# Watering_System_3_1.net
KiCad netlist of a schematic drawn in EAGLE
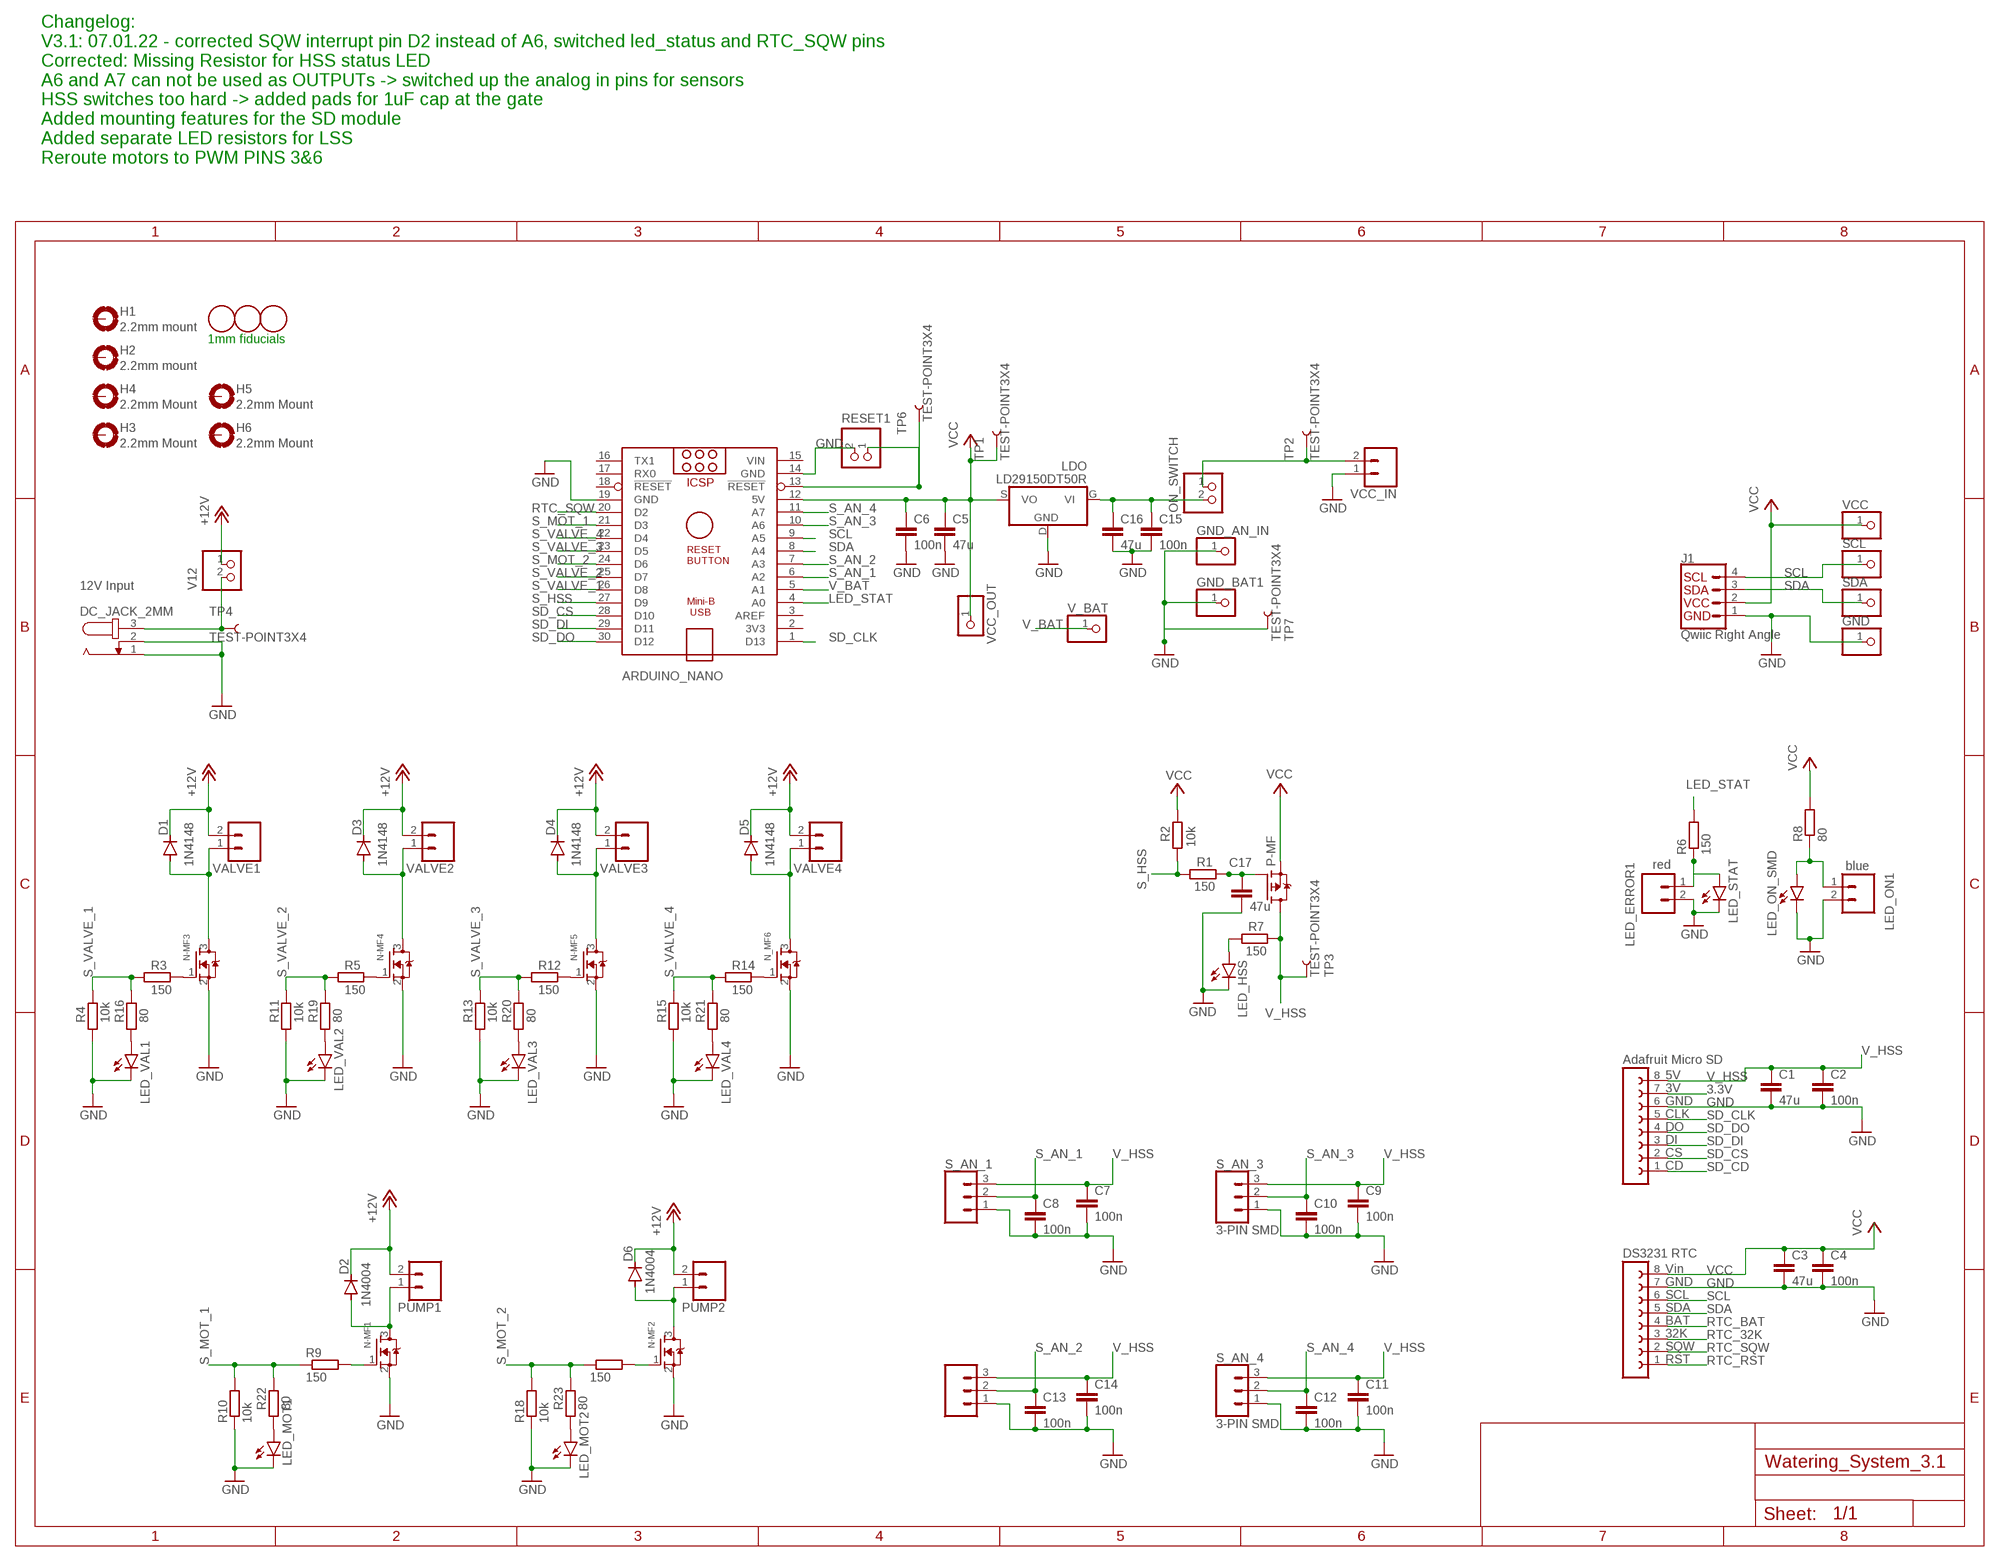
[diagram p0: schematic, sheet 1]

(export (version "E")
  (design (tool "Eeschema 10.0.6"))
  (components
    (comp (ref "ARDUINO_NANO")
      (value "ARDUINO_NANO")
      (footprint "eagle-import:ARDUINO_NANO")
      (libsource (lib "eagle-import") (part "ARDUINO_NANO"))
    )
    (comp (ref "C1")
      (value "47u")
      (footprint "eagle-import:C0805")
      (libsource (lib "eagle-import") (part "C-EUC0805"))
    )
    (comp (ref "C2")
      (value "100n")
      (footprint "eagle-import:C0805")
      (libsource (lib "eagle-import") (part "C-EUC0805"))
    )
    (comp (ref "C3")
      (value "47u")
      (footprint "eagle-import:C0805")
      (libsource (lib "eagle-import") (part "C-EUC0805"))
    )
    (comp (ref "C4")
      (value "100n")
      (footprint "eagle-import:C0805")
      (libsource (lib "eagle-import") (part "C-EUC0805"))
    )
    (comp (ref "C5")
      (value "47u")
      (footprint "eagle-import:C0805")
      (libsource (lib "eagle-import") (part "C-EUC0805"))
    )
    (comp (ref "C6")
      (value "100n")
      (footprint "eagle-import:C0805")
      (libsource (lib "eagle-import") (part "C-EUC0805"))
    )
    (comp (ref "C7")
      (value "100n")
      (footprint "eagle-import:C0805")
      (libsource (lib "eagle-import") (part "C-EUC0805"))
    )
    (comp (ref "C8")
      (value "100n")
      (footprint "eagle-import:C0805")
      (libsource (lib "eagle-import") (part "C-EUC0805"))
    )
    (comp (ref "C9")
      (value "100n")
      (footprint "eagle-import:C0805")
      (libsource (lib "eagle-import") (part "C-EUC0805"))
    )
    (comp (ref "C10")
      (value "100n")
      (footprint "eagle-import:C0805")
      (libsource (lib "eagle-import") (part "C-EUC0805"))
    )
    (comp (ref "C11")
      (value "100n")
      (footprint "eagle-import:C0805")
      (libsource (lib "eagle-import") (part "C-EUC0805"))
    )
    (comp (ref "C12")
      (value "100n")
      (footprint "eagle-import:C0805")
      (libsource (lib "eagle-import") (part "C-EUC0805"))
    )
    (comp (ref "C13")
      (value "100n")
      (footprint "eagle-import:C0805")
      (libsource (lib "eagle-import") (part "C-EUC0805"))
    )
    (comp (ref "C14")
      (value "100n")
      (footprint "eagle-import:C0805")
      (libsource (lib "eagle-import") (part "C-EUC0805"))
    )
    (comp (ref "C15")
      (value "100n")
      (footprint "eagle-import:C0805")
      (libsource (lib "eagle-import") (part "C-EUC0805"))
    )
    (comp (ref "C16")
      (value "47u")
      (footprint "eagle-import:C0805")
      (libsource (lib "eagle-import") (part "C-EUC0805"))
    )
    (comp (ref "C17")
      (value "47u")
      (footprint "eagle-import:C0805")
      (libsource (lib "eagle-import") (part "C-EUC0805"))
    )
    (comp (ref "D1")
      (value "1N4148")
      (footprint "eagle-import:DO35-7")
      (libsource (lib "eagle-import") (part "1N4148DO35-7"))
    )
    (comp (ref "D2")
      (value "1N4004")
      (footprint "eagle-import:DO41-10")
      (libsource (lib "eagle-import") (part "1N4004"))
    )
    (comp (ref "D3")
      (value "1N4148")
      (footprint "eagle-import:DO35-7")
      (libsource (lib "eagle-import") (part "1N4148DO35-7"))
    )
    (comp (ref "D4")
      (value "1N4148")
      (footprint "eagle-import:DO35-7")
      (libsource (lib "eagle-import") (part "1N4148DO35-7"))
    )
    (comp (ref "D5")
      (value "1N4148")
      (footprint "eagle-import:DO35-7")
      (libsource (lib "eagle-import") (part "1N4148DO35-7"))
    )
    (comp (ref "D6")
      (value "1N4004")
      (footprint "eagle-import:DO41-10")
      (libsource (lib "eagle-import") (part "1N4004"))
    )
    (comp (ref "DC_JACK_2MM")
      (value "12V Input")
      (footprint "eagle-import:SPC4077")
      (libsource (lib "eagle-import") (part "JACK-PLUG0"))
    )
    (comp (ref "GND")
      (value "PINHD-1X1")
      (footprint "eagle-import:1X01")
      (libsource (lib "eagle-import") (part "PINHD-1X1"))
    )
    (comp (ref "GND_AN_IN")
      (value "PINHD-1X1")
      (footprint "eagle-import:1X01")
      (libsource (lib "eagle-import") (part "PINHD-1X1"))
    )
    (comp (ref "GND_BAT1")
      (value "PINHD-1X1")
      (footprint "eagle-import:1X01")
      (libsource (lib "eagle-import") (part "PINHD-1X1"))
    )
    (comp (ref "H1")
      (value "2.2mm mount")
      (footprint "eagle-import:2,2-PAD")
      (libsource (lib "eagle-import") (part "MOUNT-PAD-ROUND2.8"))
    )
    (comp (ref "H2")
      (value "2.2mm mount")
      (footprint "eagle-import:2,2-PAD")
      (libsource (lib "eagle-import") (part "MOUNT-PAD-ROUND2.8"))
    )
    (comp (ref "H3")
      (value "2.2mm Mount")
      (footprint "eagle-import:2,2-PAD")
      (libsource (lib "eagle-import") (part "MOUNT-PAD-ROUND2.8"))
    )
    (comp (ref "H4")
      (value "2.2mm Mount")
      (footprint "eagle-import:2,2-PAD")
      (libsource (lib "eagle-import") (part "MOUNT-PAD-ROUND2.8"))
    )
    (comp (ref "H5")
      (value "2.2mm Mount")
      (footprint "eagle-import:2,2-PAD")
      (libsource (lib "eagle-import") (part "MOUNT-PAD-ROUND2.8"))
    )
    (comp (ref "H6")
      (value "2.2mm Mount")
      (footprint "eagle-import:2,2-PAD")
      (libsource (lib "eagle-import") (part "MOUNT-PAD-ROUND2.8"))
    )
    (comp (ref "J1")
      (value "Qwiic Right Angle")
      (footprint "eagle-import:1X04_1MM_RA")
      (libsource (lib "eagle-import") (part "I2C_STANDARDQWIIC"))
    )
    (comp (ref "LDO")
      (value "LD29150DT50R")
      (footprint "eagle-import:DPACK_2")
      (libsource (lib "eagle-import") (part "LD29150DT50R"))
    )
    (comp (ref "LED_ERROR1")
      (value "red")
      (footprint "eagle-import:1X02")
      (libsource (lib "eagle-import") (part "CONN_02"))
    )
    (comp (ref "LED_HSS")
      (value "LEDCHIPLED_0805")
      (footprint "eagle-import:CHIPLED_0805")
      (libsource (lib "eagle-import") (part "LEDCHIPLED_0805"))
    )
    (comp (ref "LED_MOT1")
      (value "LEDCHIPLED_0805")
      (footprint "eagle-import:CHIPLED_0805")
      (libsource (lib "eagle-import") (part "LEDCHIPLED_0805"))
    )
    (comp (ref "LED_MOT2")
      (value "LEDCHIPLED_0805")
      (footprint "eagle-import:CHIPLED_0805")
      (libsource (lib "eagle-import") (part "LEDCHIPLED_0805"))
    )
    (comp (ref "LED_ON1")
      (value "blue")
      (footprint "eagle-import:1X02")
      (libsource (lib "eagle-import") (part "CONN_02"))
    )
    (comp (ref "LED_ON_SMD")
      (value "LEDCHIPLED_0805")
      (footprint "eagle-import:CHIPLED_0805")
      (libsource (lib "eagle-import") (part "LEDCHIPLED_0805"))
    )
    (comp (ref "LED_STAT")
      (value "LEDCHIPLED_0805")
      (footprint "eagle-import:CHIPLED_0805")
      (libsource (lib "eagle-import") (part "LEDCHIPLED_0805"))
    )
    (comp (ref "LED_VAL1")
      (value "LEDCHIPLED_0805")
      (footprint "eagle-import:CHIPLED_0805")
      (libsource (lib "eagle-import") (part "LEDCHIPLED_0805"))
    )
    (comp (ref "LED_VAL2")
      (value "LEDCHIPLED_0805")
      (footprint "eagle-import:CHIPLED_0805")
      (libsource (lib "eagle-import") (part "LEDCHIPLED_0805"))
    )
    (comp (ref "LED_VAL3")
      (value "LEDCHIPLED_0805")
      (footprint "eagle-import:CHIPLED_0805")
      (libsource (lib "eagle-import") (part "LEDCHIPLED_0805"))
    )
    (comp (ref "LED_VAL4")
      (value "LEDCHIPLED_0805")
      (footprint "eagle-import:CHIPLED_0805")
      (libsource (lib "eagle-import") (part "LEDCHIPLED_0805"))
    )
    (comp (ref "N-MF1")
      (value "IRLML6244TRPBF")
      (footprint "eagle-import:SOT23R_INFINEON")
      (libsource (lib "eagle-import") (part "IRLML6244TRPBF"))
    )
    (comp (ref "N-MF2")
      (value "IRLML6244TRPBF")
      (footprint "eagle-import:SOT23R_INFINEON")
      (libsource (lib "eagle-import") (part "IRLML6244TRPBF"))
    )
    (comp (ref "N-MF3")
      (value "IRLML6244TRPBF")
      (footprint "eagle-import:SOT23R_INFINEON")
      (libsource (lib "eagle-import") (part "IRLML6244TRPBF"))
    )
    (comp (ref "N-MF4")
      (value "IRLML6244TRPBF")
      (footprint "eagle-import:SOT23R_INFINEON")
      (libsource (lib "eagle-import") (part "IRLML6244TRPBF"))
    )
    (comp (ref "N-MF5")
      (value "IRLML6244TRPBF")
      (footprint "eagle-import:SOT23R_INFINEON")
      (libsource (lib "eagle-import") (part "IRLML6244TRPBF"))
    )
    (comp (ref "N_MF6")
      (value "IRLML6244TRPBF")
      (footprint "eagle-import:SOT23R_INFINEON")
      (libsource (lib "eagle-import") (part "IRLML6244TRPBF"))
    )
    (comp (ref "ON_SWITCH")
      (value "toggle_breakout")
      (footprint "eagle-import:1X02")
      (libsource (lib "eagle-import") (part "PINHD-1X2"))
    )
    (comp (ref "P-MF")
      (value "IRLML2244TRPBF")
      (footprint "eagle-import:SOT23R_INFINEON")
      (libsource (lib "eagle-import") (part "IRLML2244TRPBF"))
    )
    (comp (ref "PUMP1")
      (value "CONN_02-JST-2MM-SMT")
      (footprint "eagle-import:JST-2-SMD")
      (libsource (lib "eagle-import") (part "CONN_02-JST-2MM-SMT"))
    )
    (comp (ref "PUMP2")
      (value "CONN_02-JST-2MM-SMT")
      (footprint "eagle-import:JST-2-SMD")
      (libsource (lib "eagle-import") (part "CONN_02-JST-2MM-SMT"))
    )
    (comp (ref "R1")
      (value "150")
      (footprint "eagle-import:R0805")
      (libsource (lib "eagle-import") (part "R-EU_R0805"))
    )
    (comp (ref "R2")
      (value "10k")
      (footprint "eagle-import:R0805")
      (libsource (lib "eagle-import") (part "R-EU_R0805"))
    )
    (comp (ref "R3")
      (value "150")
      (footprint "eagle-import:R0805")
      (libsource (lib "eagle-import") (part "R-EU_R0805"))
    )
    (comp (ref "R4")
      (value "10k")
      (footprint "eagle-import:R0805")
      (libsource (lib "eagle-import") (part "R-EU_R0805"))
    )
    (comp (ref "R5")
      (value "150")
      (footprint "eagle-import:R0805")
      (libsource (lib "eagle-import") (part "R-EU_R0805"))
    )
    (comp (ref "R6")
      (value "150")
      (footprint "eagle-import:R0805")
      (libsource (lib "eagle-import") (part "R-EU_R0805"))
    )
    (comp (ref "R7")
      (value "150")
      (footprint "eagle-import:R0805")
      (libsource (lib "eagle-import") (part "R-EU_R0805"))
    )
    (comp (ref "R8")
      (value "80")
      (footprint "eagle-import:R0805")
      (libsource (lib "eagle-import") (part "R-EU_R0805"))
    )
    (comp (ref "R9")
      (value "150")
      (footprint "eagle-import:R0805")
      (libsource (lib "eagle-import") (part "R-EU_R0805"))
    )
    (comp (ref "R10")
      (value "10k")
      (footprint "eagle-import:R0805")
      (libsource (lib "eagle-import") (part "R-EU_R0805"))
    )
    (comp (ref "R11")
      (value "10k")
      (footprint "eagle-import:R0805")
      (libsource (lib "eagle-import") (part "R-EU_R0805"))
    )
    (comp (ref "R12")
      (value "150")
      (footprint "eagle-import:R0805")
      (libsource (lib "eagle-import") (part "R-EU_R0805"))
    )
    (comp (ref "R13")
      (value "10k")
      (footprint "eagle-import:R0805")
      (libsource (lib "eagle-import") (part "R-EU_R0805"))
    )
    (comp (ref "R14")
      (value "150")
      (footprint "eagle-import:R0805")
      (libsource (lib "eagle-import") (part "R-EU_R0805"))
    )
    (comp (ref "R15")
      (value "10k")
      (footprint "eagle-import:R0805")
      (libsource (lib "eagle-import") (part "R-EU_R0805"))
    )
    (comp (ref "R16")
      (value "80")
      (footprint "eagle-import:R0805")
      (libsource (lib "eagle-import") (part "R-EU_R0805"))
    )
    (comp (ref "R17")
      (value "150")
      (footprint "eagle-import:R0805")
      (libsource (lib "eagle-import") (part "R-EU_R0805"))
    )
    (comp (ref "R18")
      (value "10k")
      (footprint "eagle-import:R0805")
      (libsource (lib "eagle-import") (part "R-EU_R0805"))
    )
    (comp (ref "R19")
      (value "80")
      (footprint "eagle-import:R0805")
      (libsource (lib "eagle-import") (part "R-EU_R0805"))
    )
    (comp (ref "R20")
      (value "80")
      (footprint "eagle-import:R0805")
      (libsource (lib "eagle-import") (part "R-EU_R0805"))
    )
    (comp (ref "R21")
      (value "80")
      (footprint "eagle-import:R0805")
      (libsource (lib "eagle-import") (part "R-EU_R0805"))
    )
    (comp (ref "R22")
      (value "80")
      (footprint "eagle-import:R0805")
      (libsource (lib "eagle-import") (part "R-EU_R0805"))
    )
    (comp (ref "R23")
      (value "80")
      (footprint "eagle-import:R0805")
      (libsource (lib "eagle-import") (part "R-EU_R0805"))
    )
    (comp (ref "RESET1")
      (value "toggle_breakout")
      (footprint "eagle-import:1X02")
      (libsource (lib "eagle-import") (part "PINHD-1X2"))
    )
    (comp (ref "RTC")
      (value "DS3231")
      (footprint "eagle-import:RTC")
      (libsource (lib "eagle-import") (part "DS3231_RTC"))
    )
    (comp (ref "SCL")
      (value "PINHD-1X1")
      (footprint "eagle-import:1X01")
      (libsource (lib "eagle-import") (part "PINHD-1X1"))
    )
    (comp (ref "SC_CARD")
      (value "MIRCO_SD_ADAFRUITSD")
      (footprint "eagle-import:ADAFRUIT_SD")
      (libsource (lib "eagle-import") (part "MIRCO_SD_ADAFRUITSD"))
    )
    (comp (ref "SDA")
      (value "PINHD-1X1")
      (footprint "eagle-import:1X01")
      (libsource (lib "eagle-import") (part "PINHD-1X1"))
    )
    (comp (ref "S_AN_1")
      (value "3-PIN SMD")
      (footprint "eagle-import:JST-3-SMD")
      (libsource (lib "eagle-import") (part "CONN_03JST-SMD"))
    )
    (comp (ref "S_AN_2")
      (value "3-PIN SMD")
      (footprint "eagle-import:JST-3-SMD")
      (libsource (lib "eagle-import") (part "CONN_03JST-SMD"))
    )
    (comp (ref "S_AN_3")
      (value "3-PIN SMD")
      (footprint "eagle-import:JST-3-SMD")
      (libsource (lib "eagle-import") (part "CONN_03JST-SMD"))
    )
    (comp (ref "S_AN_4")
      (value "3-PIN SMD")
      (footprint "eagle-import:JST-3-SMD")
      (libsource (lib "eagle-import") (part "CONN_03JST-SMD"))
    )
    (comp (ref "TP1")
      (value "TEST-POINT3X4")
      (footprint "eagle-import:PAD.03X.04")
      (libsource (lib "eagle-import") (part "TEST-POINT3X4"))
    )
    (comp (ref "TP2")
      (value "TEST-POINT3X4")
      (footprint "eagle-import:PAD.03X.04")
      (libsource (lib "eagle-import") (part "TEST-POINT3X4"))
    )
    (comp (ref "TP3")
      (value "TEST-POINT3X4")
      (footprint "eagle-import:PAD.03X.04")
      (libsource (lib "eagle-import") (part "TEST-POINT3X4"))
    )
    (comp (ref "TP4")
      (value "TEST-POINT3X4")
      (footprint "eagle-import:PAD.03X.04")
      (libsource (lib "eagle-import") (part "TEST-POINT3X4"))
    )
    (comp (ref "TP6")
      (value "TEST-POINT3X4")
      (footprint "eagle-import:PAD.03X.04")
      (libsource (lib "eagle-import") (part "TEST-POINT3X4"))
    )
    (comp (ref "TP7")
      (value "TEST-POINT3X4")
      (footprint "eagle-import:PAD.03X.04")
      (libsource (lib "eagle-import") (part "TEST-POINT3X4"))
    )
    (comp (ref "U$1")
      (value "FIDUCIAL")
      (footprint "eagle-import:FIDUCIAL_1MM")
      (libsource (lib "eagle-import") (part "FIDUCIAL"))
    )
    (comp (ref "U$2")
      (value "FIDUCIAL")
      (footprint "eagle-import:FIDUCIAL_1MM")
      (libsource (lib "eagle-import") (part "FIDUCIAL"))
    )
    (comp (ref "U$3")
      (value "FIDUCIAL")
      (footprint "eagle-import:FIDUCIAL_1MM")
      (libsource (lib "eagle-import") (part "FIDUCIAL"))
    )
    (comp (ref "V12")
      (value "toggle_breakout")
      (footprint "eagle-import:1X02")
      (libsource (lib "eagle-import") (part "PINHD-1X2"))
    )
    (comp (ref "VALVE1")
      (value "CONN_02-JST-2MM-SMT")
      (footprint "eagle-import:JST-2-SMD")
      (libsource (lib "eagle-import") (part "CONN_02-JST-2MM-SMT"))
    )
    (comp (ref "VALVE2")
      (value "CONN_02-JST-2MM-SMT")
      (footprint "eagle-import:JST-2-SMD")
      (libsource (lib "eagle-import") (part "CONN_02-JST-2MM-SMT"))
    )
    (comp (ref "VALVE3")
      (value "CONN_02-JST-2MM-SMT")
      (footprint "eagle-import:JST-2-SMD")
      (libsource (lib "eagle-import") (part "CONN_02-JST-2MM-SMT"))
    )
    (comp (ref "VALVE4")
      (value "CONN_02-JST-2MM-SMT")
      (footprint "eagle-import:JST-2-SMD")
      (libsource (lib "eagle-import") (part "CONN_02-JST-2MM-SMT"))
    )
    (comp (ref "VCC")
      (value "PINHD-1X1")
      (footprint "eagle-import:1X01")
      (libsource (lib "eagle-import") (part "PINHD-1X1"))
    )
    (comp (ref "VCC_IN")
      (value "CONN_02-JST-2MM-SMT")
      (footprint "eagle-import:JST-2-SMD")
      (libsource (lib "eagle-import") (part "CONN_02-JST-2MM-SMT"))
    )
    (comp (ref "VCC_OUT")
      (value "PINHD-1X1")
      (footprint "eagle-import:1X01")
      (libsource (lib "eagle-import") (part "PINHD-1X1"))
    )
    (comp (ref "V_BAT")
      (value "PINHD-1X1")
      (footprint "eagle-import:1X01")
      (libsource (lib "eagle-import") (part "PINHD-1X1"))
    )
  )
  (nets
    (net (code "1") (name "+12V") (class "Default")
      (node (ref "D1") (pin "C") (pinfunction "C_C") (pintype "passive"))
      (node (ref "D2") (pin "C") (pinfunction "C_C") (pintype "passive"))
      (node (ref "D3") (pin "C") (pinfunction "C_C") (pintype "passive"))
      (node (ref "D4") (pin "C") (pinfunction "C_C") (pintype "passive"))
      (node (ref "D5") (pin "C") (pinfunction "C_C") (pintype "passive"))
      (node (ref "D6") (pin "C") (pinfunction "C_C") (pintype "passive"))
      (node (ref "PUMP1") (pin "2") (pinfunction "1_2") (pintype "passive"))
      (node (ref "PUMP2") (pin "2") (pinfunction "1_2") (pintype "passive"))
      (node (ref "V12") (pin "1") (pinfunction "1_1") (pintype "passive"))
      (node (ref "VALVE1") (pin "2") (pinfunction "1_2") (pintype "passive"))
      (node (ref "VALVE2") (pin "2") (pinfunction "1_2") (pintype "passive"))
      (node (ref "VALVE3") (pin "2") (pinfunction "1_2") (pintype "passive"))
      (node (ref "VALVE4") (pin "2") (pinfunction "1_2") (pintype "passive"))
    )
    (net (code "2") (name "/3.3V") (class "Default")
      (node (ref "SC_CARD") (pin "7") (pinfunction "3V_7") (pintype "passive"))
    )
    (net (code "3") (name "/LED_STAT") (class "Default")
      (node (ref "ARDUINO_NANO") (pin "4") (pinfunction "A0_4") (pintype "bidirectional"))
      (node (ref "R6") (pin "2") (pinfunction "2_2") (pintype "passive"))
    )
    (net (code "4") (name "/RTC_32K") (class "Default")
      (node (ref "RTC") (pin "3") (pinfunction "32K_3") (pintype "passive"))
    )
    (net (code "5") (name "/RTC_BAT") (class "Default")
      (node (ref "RTC") (pin "4") (pinfunction "BAT_4") (pintype "passive"))
    )
    (net (code "6") (name "/RTC_RST") (class "Default")
      (node (ref "RTC") (pin "1") (pinfunction "RST_1") (pintype "passive"))
    )
    (net (code "7") (name "/RTC_SQW") (class "Default")
      (node (ref "ARDUINO_NANO") (pin "20") (pinfunction "D2_20") (pintype "bidirectional"))
      (node (ref "RTC") (pin "2") (pinfunction "SQW_2") (pintype "passive"))
    )
    (net (code "8") (name "/SCL") (class "Default")
      (node (ref "ARDUINO_NANO") (pin "9") (pinfunction "A5_9") (pintype "bidirectional"))
      (node (ref "J1") (pin "4") (pinfunction "4_4") (pintype "passive"))
      (node (ref "RTC") (pin "6") (pinfunction "SCL_6") (pintype "passive"))
      (node (ref "SCL") (pin "1") (pinfunction "1_1") (pintype "passive"))
    )
    (net (code "9") (name "/SDA") (class "Default")
      (node (ref "ARDUINO_NANO") (pin "8") (pinfunction "A4_8") (pintype "bidirectional"))
      (node (ref "J1") (pin "3") (pinfunction "3_3") (pintype "passive"))
      (node (ref "RTC") (pin "5") (pinfunction "SDA_5") (pintype "passive"))
      (node (ref "SDA") (pin "1") (pinfunction "1_1") (pintype "passive"))
    )
    (net (code "10") (name "/SD_CD") (class "Default")
      (node (ref "SC_CARD") (pin "1") (pinfunction "CD_1") (pintype "passive"))
    )
    (net (code "11") (name "/SD_CLK") (class "Default")
      (node (ref "ARDUINO_NANO") (pin "1") (pinfunction "D13_1") (pintype "bidirectional"))
      (node (ref "SC_CARD") (pin "5") (pinfunction "CLK_5") (pintype "passive"))
    )
    (net (code "12") (name "/SD_CS") (class "Default")
      (node (ref "ARDUINO_NANO") (pin "28") (pinfunction "D10_28") (pintype "bidirectional"))
      (node (ref "SC_CARD") (pin "2") (pinfunction "CS_2") (pintype "passive"))
    )
    (net (code "13") (name "/SD_DI") (class "Default")
      (node (ref "ARDUINO_NANO") (pin "29") (pinfunction "D11_29") (pintype "bidirectional"))
      (node (ref "SC_CARD") (pin "3") (pinfunction "DI_3") (pintype "passive"))
    )
    (net (code "14") (name "/SD_DO") (class "Default")
      (node (ref "ARDUINO_NANO") (pin "30") (pinfunction "D12_30") (pintype "bidirectional"))
      (node (ref "SC_CARD") (pin "4") (pinfunction "DO_4") (pintype "passive"))
    )
    (net (code "15") (name "/S_AN_1") (class "Default")
      (node (ref "ARDUINO_NANO") (pin "6") (pinfunction "A2_6") (pintype "bidirectional"))
      (node (ref "C8") (pin "1") (pinfunction "1_1") (pintype "passive"))
      (node (ref "S_AN_1") (pin "2") (pinfunction "2_2") (pintype "passive"))
    )
    (net (code "16") (name "/S_AN_2") (class "Default")
      (node (ref "ARDUINO_NANO") (pin "7") (pinfunction "A3_7") (pintype "bidirectional"))
      (node (ref "C13") (pin "1") (pinfunction "1_1") (pintype "passive"))
      (node (ref "S_AN_2") (pin "2") (pinfunction "2_2") (pintype "passive"))
    )
    (net (code "17") (name "/S_AN_3") (class "Default")
      (node (ref "ARDUINO_NANO") (pin "10") (pinfunction "A6_10") (pintype "bidirectional"))
      (node (ref "C10") (pin "1") (pinfunction "1_1") (pintype "passive"))
      (node (ref "S_AN_3") (pin "2") (pinfunction "2_2") (pintype "passive"))
    )
    (net (code "18") (name "/S_AN_4") (class "Default")
      (node (ref "ARDUINO_NANO") (pin "11") (pinfunction "A7_11") (pintype "bidirectional"))
      (node (ref "C12") (pin "1") (pinfunction "1_1") (pintype "passive"))
      (node (ref "S_AN_4") (pin "2") (pinfunction "2_2") (pintype "passive"))
    )
    (net (code "19") (name "/S_HSS") (class "Default")
      (node (ref "ARDUINO_NANO") (pin "27") (pinfunction "D9_27") (pintype "bidirectional"))
      (node (ref "R1") (pin "1") (pinfunction "1_1") (pintype "passive"))
      (node (ref "R2") (pin "1") (pinfunction "1_1") (pintype "passive"))
    )
    (net (code "20") (name "/S_MOT_1") (class "Default")
      (node (ref "ARDUINO_NANO") (pin "21") (pinfunction "D3_21") (pintype "bidirectional"))
      (node (ref "R10") (pin "2") (pinfunction "2_2") (pintype "passive"))
      (node (ref "R22") (pin "2") (pinfunction "2_2") (pintype "passive"))
      (node (ref "R9") (pin "1") (pinfunction "1_1") (pintype "passive"))
    )
    (net (code "21") (name "/S_MOT_2") (class "Default")
      (node (ref "ARDUINO_NANO") (pin "24") (pinfunction "D6_24") (pintype "bidirectional"))
      (node (ref "R17") (pin "1") (pinfunction "1_1") (pintype "passive"))
      (node (ref "R18") (pin "2") (pinfunction "2_2") (pintype "passive"))
      (node (ref "R23") (pin "2") (pinfunction "2_2") (pintype "passive"))
    )
    (net (code "22") (name "/S_VALVE_1") (class "Default")
      (node (ref "ARDUINO_NANO") (pin "26") (pinfunction "D8_26") (pintype "bidirectional"))
      (node (ref "R16") (pin "2") (pinfunction "2_2") (pintype "passive"))
      (node (ref "R3") (pin "1") (pinfunction "1_1") (pintype "passive"))
      (node (ref "R4") (pin "2") (pinfunction "2_2") (pintype "passive"))
    )
    (net (code "23") (name "/S_VALVE_2") (class "Default")
      (node (ref "ARDUINO_NANO") (pin "25") (pinfunction "D7_25") (pintype "bidirectional"))
      (node (ref "R11") (pin "2") (pinfunction "2_2") (pintype "passive"))
      (node (ref "R19") (pin "2") (pinfunction "2_2") (pintype "passive"))
      (node (ref "R5") (pin "1") (pinfunction "1_1") (pintype "passive"))
    )
    (net (code "24") (name "/S_VALVE_3") (class "Default")
      (node (ref "ARDUINO_NANO") (pin "23") (pinfunction "D5_23") (pintype "bidirectional"))
      (node (ref "R12") (pin "1") (pinfunction "1_1") (pintype "passive"))
      (node (ref "R13") (pin "2") (pinfunction "2_2") (pintype "passive"))
      (node (ref "R20") (pin "2") (pinfunction "2_2") (pintype "passive"))
    )
    (net (code "25") (name "/S_VALVE_4") (class "Default")
      (node (ref "ARDUINO_NANO") (pin "22") (pinfunction "D4_22") (pintype "bidirectional"))
      (node (ref "R14") (pin "1") (pinfunction "1_1") (pintype "passive"))
      (node (ref "R15") (pin "2") (pinfunction "2_2") (pintype "passive"))
      (node (ref "R21") (pin "2") (pinfunction "2_2") (pintype "passive"))
    )
    (net (code "26") (name "/VIN") (class "Default")
      (node (ref "ARDUINO_NANO") (pin "15") (pinfunction "VIN_15") (pintype "power_in"))
    )
    (net (code "27") (name "/V_BAT") (class "Default")
      (node (ref "ARDUINO_NANO") (pin "5") (pinfunction "A1_5") (pintype "bidirectional"))
      (node (ref "V_BAT") (pin "1") (pinfunction "1_1") (pintype "passive"))
    )
    (net (code "28") (name "/V_HSS") (class "Default")
      (node (ref "C1") (pin "1") (pinfunction "1_1") (pintype "passive"))
      (node (ref "C11") (pin "1") (pinfunction "1_1") (pintype "passive"))
      (node (ref "C14") (pin "1") (pinfunction "1_1") (pintype "passive"))
      (node (ref "C2") (pin "1") (pinfunction "1_1") (pintype "passive"))
      (node (ref "C7") (pin "1") (pinfunction "1_1") (pintype "passive"))
      (node (ref "C9") (pin "1") (pinfunction "1_1") (pintype "passive"))
      (node (ref "P-MF") (pin "3") (pinfunction "D_3") (pintype "passive"))
      (node (ref "R7") (pin "2") (pinfunction "2_2") (pintype "passive"))
      (node (ref "SC_CARD") (pin "8") (pinfunction "5V_8") (pintype "passive"))
      (node (ref "S_AN_1") (pin "3") (pinfunction "3_3") (pintype "passive"))
      (node (ref "S_AN_2") (pin "3") (pinfunction "3_3") (pintype "passive"))
      (node (ref "S_AN_3") (pin "3") (pinfunction "3_3") (pintype "passive"))
      (node (ref "S_AN_4") (pin "3") (pinfunction "3_3") (pintype "passive"))
      (node (ref "TP3") (pin "P$1") (pinfunction "1_P$1") (pintype "bidirectional"))
    )
    (net (code "29") (name "GND") (class "Default")
      (node (ref "ARDUINO_NANO") (pin "14") (pinfunction "GND_14") (pintype "power_in"))
      (node (ref "ARDUINO_NANO") (pin "19") (pinfunction "GND_19") (pintype "power_in"))
      (node (ref "C1") (pin "2") (pinfunction "2_2") (pintype "passive"))
      (node (ref "C10") (pin "2") (pinfunction "2_2") (pintype "passive"))
      (node (ref "C11") (pin "2") (pinfunction "2_2") (pintype "passive"))
      (node (ref "C12") (pin "2") (pinfunction "2_2") (pintype "passive"))
      (node (ref "C13") (pin "2") (pinfunction "2_2") (pintype "passive"))
      (node (ref "C14") (pin "2") (pinfunction "2_2") (pintype "passive"))
      (node (ref "C15") (pin "2") (pinfunction "2_2") (pintype "passive"))
      (node (ref "C16") (pin "2") (pinfunction "2_2") (pintype "passive"))
      (node (ref "C17") (pin "2") (pinfunction "2_2") (pintype "passive"))
      (node (ref "C2") (pin "2") (pinfunction "2_2") (pintype "passive"))
      (node (ref "C3") (pin "2") (pinfunction "2_2") (pintype "passive"))
      (node (ref "C4") (pin "2") (pinfunction "2_2") (pintype "passive"))
      (node (ref "C5") (pin "2") (pinfunction "2_2") (pintype "passive"))
      (node (ref "C6") (pin "2") (pinfunction "2_2") (pintype "passive"))
      (node (ref "C7") (pin "2") (pinfunction "2_2") (pintype "passive"))
      (node (ref "C8") (pin "2") (pinfunction "2_2") (pintype "passive"))
      (node (ref "C9") (pin "2") (pinfunction "2_2") (pintype "passive"))
      (node (ref "DC_JACK_2MM") (pin "1") (pinfunction "1_1") (pintype "passive"))
      (node (ref "DC_JACK_2MM") (pin "2") (pinfunction "2_2") (pintype "passive"))
      (node (ref "GND") (pin "1") (pinfunction "1_1") (pintype "passive"))
      (node (ref "GND_AN_IN") (pin "1") (pinfunction "1_1") (pintype "passive"))
      (node (ref "GND_BAT1") (pin "1") (pinfunction "1_1") (pintype "passive"))
      (node (ref "J1") (pin "1") (pinfunction "1_1") (pintype "power_in"))
      (node (ref "LDO") (pin "D") (pinfunction "GND_D") (pintype "passive"))
      (node (ref "LED_ERROR1") (pin "2") (pinfunction "2_2") (pintype "passive"))
      (node (ref "LED_HSS") (pin "C") (pinfunction "C_C") (pintype "passive"))
      (node (ref "LED_MOT1") (pin "C") (pinfunction "C_C") (pintype "passive"))
      (node (ref "LED_MOT2") (pin "C") (pinfunction "C_C") (pintype "passive"))
      (node (ref "LED_ON1") (pin "2") (pinfunction "2_2") (pintype "passive"))
      (node (ref "LED_ON_SMD") (pin "C") (pinfunction "C_C") (pintype "passive"))
      (node (ref "LED_STAT") (pin "C") (pinfunction "C_C") (pintype "passive"))
      (node (ref "LED_VAL1") (pin "C") (pinfunction "C_C") (pintype "passive"))
      (node (ref "LED_VAL2") (pin "C") (pinfunction "C_C") (pintype "passive"))
      (node (ref "LED_VAL3") (pin "C") (pinfunction "C_C") (pintype "passive"))
      (node (ref "LED_VAL4") (pin "C") (pinfunction "C_C") (pintype "passive"))
      (node (ref "N-MF1") (pin "2") (pinfunction "S_2") (pintype "bidirectional"))
      (node (ref "N-MF2") (pin "2") (pinfunction "S_2") (pintype "bidirectional"))
      (node (ref "N-MF3") (pin "2") (pinfunction "S_2") (pintype "bidirectional"))
      (node (ref "N-MF4") (pin "2") (pinfunction "S_2") (pintype "bidirectional"))
      (node (ref "N-MF5") (pin "2") (pinfunction "S_2") (pintype "bidirectional"))
      (node (ref "N_MF6") (pin "2") (pinfunction "S_2") (pintype "bidirectional"))
      (node (ref "R10") (pin "1") (pinfunction "1_1") (pintype "passive"))
      (node (ref "R11") (pin "1") (pinfunction "1_1") (pintype "passive"))
      (node (ref "R13") (pin "1") (pinfunction "1_1") (pintype "passive"))
      (node (ref "R15") (pin "1") (pinfunction "1_1") (pintype "passive"))
      (node (ref "R18") (pin "1") (pinfunction "1_1") (pintype "passive"))
      (node (ref "R4") (pin "1") (pinfunction "1_1") (pintype "passive"))
      (node (ref "RESET1") (pin "2") (pinfunction "2_2") (pintype "passive"))
      (node (ref "RTC") (pin "7") (pinfunction "GND_7") (pintype "passive"))
      (node (ref "SC_CARD") (pin "6") (pinfunction "GND_6") (pintype "passive"))
      (node (ref "S_AN_1") (pin "1") (pinfunction "1_1") (pintype "passive"))
      (node (ref "S_AN_2") (pin "1") (pinfunction "1_1") (pintype "passive"))
      (node (ref "S_AN_3") (pin "1") (pinfunction "1_1") (pintype "passive"))
      (node (ref "S_AN_4") (pin "1") (pinfunction "1_1") (pintype "passive"))
      (node (ref "TP7") (pin "P$1") (pinfunction "1_P$1") (pintype "bidirectional"))
      (node (ref "VCC_IN") (pin "1") (pinfunction "2_1") (pintype "passive"))
    )
    (net (code "30") (name "Net-(LDO-VI)") (class "Default")
      (node (ref "C15") (pin "1") (pinfunction "1_1") (pintype "passive"))
      (node (ref "C16") (pin "1") (pinfunction "1_1") (pintype "passive"))
      (node (ref "LDO") (pin "G") (pinfunction "VI_G") (pintype "input"))
      (node (ref "ON_SWITCH") (pin "2") (pinfunction "2_2") (pintype "passive"))
    )
    (net (code "31") (name "Net-(LED_ERROR1-Pad1)") (class "Default")
      (node (ref "LED_ERROR1") (pin "1") (pinfunction "1_1") (pintype "passive"))
      (node (ref "LED_STAT") (pin "A") (pinfunction "A_A") (pintype "passive"))
      (node (ref "R6") (pin "1") (pinfunction "1_1") (pintype "passive"))
    )
    (net (code "32") (name "Net-(LED_HSS-PadA)") (class "Default")
      (node (ref "LED_HSS") (pin "A") (pinfunction "A_A") (pintype "passive"))
      (node (ref "R7") (pin "1") (pinfunction "1_1") (pintype "passive"))
    )
    (net (code "33") (name "Net-(LED_MOT1-PadA)") (class "Default")
      (node (ref "LED_MOT1") (pin "A") (pinfunction "A_A") (pintype "passive"))
      (node (ref "R22") (pin "1") (pinfunction "1_1") (pintype "passive"))
    )
    (net (code "34") (name "Net-(LED_MOT2-PadA)") (class "Default")
      (node (ref "LED_MOT2") (pin "A") (pinfunction "A_A") (pintype "passive"))
      (node (ref "R23") (pin "1") (pinfunction "1_1") (pintype "passive"))
    )
    (net (code "35") (name "Net-(LED_ON1-Pad1)") (class "Default")
      (node (ref "LED_ON1") (pin "1") (pinfunction "1_1") (pintype "passive"))
      (node (ref "LED_ON_SMD") (pin "A") (pinfunction "A_A") (pintype "passive"))
      (node (ref "R8") (pin "1") (pinfunction "1_1") (pintype "passive"))
    )
    (net (code "36") (name "Net-(LED_VAL1-PadA)") (class "Default")
      (node (ref "LED_VAL1") (pin "A") (pinfunction "A_A") (pintype "passive"))
      (node (ref "R16") (pin "1") (pinfunction "1_1") (pintype "passive"))
    )
    (net (code "37") (name "Net-(LED_VAL2-PadA)") (class "Default")
      (node (ref "LED_VAL2") (pin "A") (pinfunction "A_A") (pintype "passive"))
      (node (ref "R19") (pin "1") (pinfunction "1_1") (pintype "passive"))
    )
    (net (code "38") (name "Net-(LED_VAL3-PadA)") (class "Default")
      (node (ref "LED_VAL3") (pin "A") (pinfunction "A_A") (pintype "passive"))
      (node (ref "R20") (pin "1") (pinfunction "1_1") (pintype "passive"))
    )
    (net (code "39") (name "Net-(LED_VAL4-PadA)") (class "Default")
      (node (ref "LED_VAL4") (pin "A") (pinfunction "A_A") (pintype "passive"))
      (node (ref "R21") (pin "1") (pinfunction "1_1") (pintype "passive"))
    )
    (net (code "40") (name "Net-(N-MF1-D)") (class "Default")
      (node (ref "D2") (pin "A") (pinfunction "A_A") (pintype "passive"))
      (node (ref "N-MF1") (pin "3") (pinfunction "D_3") (pintype "bidirectional"))
      (node (ref "PUMP1") (pin "1") (pinfunction "2_1") (pintype "passive"))
    )
    (net (code "41") (name "Net-(N-MF1-G)") (class "Default")
      (node (ref "N-MF1") (pin "1") (pinfunction "G_1") (pintype "bidirectional"))
      (node (ref "R9") (pin "2") (pinfunction "2_2") (pintype "passive"))
    )
    (net (code "42") (name "Net-(N-MF2-D)") (class "Default")
      (node (ref "D6") (pin "A") (pinfunction "A_A") (pintype "passive"))
      (node (ref "N-MF2") (pin "3") (pinfunction "D_3") (pintype "bidirectional"))
      (node (ref "PUMP2") (pin "1") (pinfunction "2_1") (pintype "passive"))
    )
    (net (code "43") (name "Net-(N-MF2-G)") (class "Default")
      (node (ref "N-MF2") (pin "1") (pinfunction "G_1") (pintype "bidirectional"))
      (node (ref "R17") (pin "2") (pinfunction "2_2") (pintype "passive"))
    )
    (net (code "44") (name "Net-(N-MF3-D)") (class "Default")
      (node (ref "D1") (pin "A") (pinfunction "A_A") (pintype "passive"))
      (node (ref "N-MF3") (pin "3") (pinfunction "D_3") (pintype "bidirectional"))
      (node (ref "VALVE1") (pin "1") (pinfunction "2_1") (pintype "passive"))
    )
    (net (code "45") (name "Net-(N-MF3-G)") (class "Default")
      (node (ref "N-MF3") (pin "1") (pinfunction "G_1") (pintype "bidirectional"))
      (node (ref "R3") (pin "2") (pinfunction "2_2") (pintype "passive"))
    )
    (net (code "46") (name "Net-(N-MF4-D)") (class "Default")
      (node (ref "D3") (pin "A") (pinfunction "A_A") (pintype "passive"))
      (node (ref "N-MF4") (pin "3") (pinfunction "D_3") (pintype "bidirectional"))
      (node (ref "VALVE2") (pin "1") (pinfunction "2_1") (pintype "passive"))
    )
    (net (code "47") (name "Net-(N-MF4-G)") (class "Default")
      (node (ref "N-MF4") (pin "1") (pinfunction "G_1") (pintype "bidirectional"))
      (node (ref "R5") (pin "2") (pinfunction "2_2") (pintype "passive"))
    )
    (net (code "48") (name "Net-(N-MF5-D)") (class "Default")
      (node (ref "D4") (pin "A") (pinfunction "A_A") (pintype "passive"))
      (node (ref "N-MF5") (pin "3") (pinfunction "D_3") (pintype "bidirectional"))
      (node (ref "VALVE3") (pin "1") (pinfunction "2_1") (pintype "passive"))
    )
    (net (code "49") (name "Net-(N-MF5-G)") (class "Default")
      (node (ref "N-MF5") (pin "1") (pinfunction "G_1") (pintype "bidirectional"))
      (node (ref "R12") (pin "2") (pinfunction "2_2") (pintype "passive"))
    )
    (net (code "50") (name "Net-(N_MF6-D)") (class "Default")
      (node (ref "D5") (pin "A") (pinfunction "A_A") (pintype "passive"))
      (node (ref "N_MF6") (pin "3") (pinfunction "D_3") (pintype "bidirectional"))
      (node (ref "VALVE4") (pin "1") (pinfunction "2_1") (pintype "passive"))
    )
    (net (code "51") (name "Net-(N_MF6-G)") (class "Default")
      (node (ref "N_MF6") (pin "1") (pinfunction "G_1") (pintype "bidirectional"))
      (node (ref "R14") (pin "2") (pinfunction "2_2") (pintype "passive"))
    )
    (net (code "52") (name "Net-(P-MF-G)") (class "Default")
      (node (ref "C17") (pin "1") (pinfunction "1_1") (pintype "passive"))
      (node (ref "P-MF") (pin "1") (pinfunction "G_1") (pintype "passive"))
      (node (ref "R1") (pin "2") (pinfunction "2_2") (pintype "passive"))
    )
    (net (code "53") (name "Net-(TP2-1)") (class "Default")
      (node (ref "ON_SWITCH") (pin "1") (pinfunction "1_1") (pintype "passive"))
      (node (ref "TP2") (pin "P$1") (pinfunction "1_P$1") (pintype "bidirectional"))
      (node (ref "VCC_IN") (pin "2") (pinfunction "1_2") (pintype "passive"))
    )
    (net (code "54") (name "Net-(TP4-1)") (class "Default")
      (node (ref "DC_JACK_2MM") (pin "3") (pinfunction "3_3") (pintype "passive"))
      (node (ref "TP4") (pin "P$1") (pinfunction "1_P$1") (pintype "bidirectional"))
      (node (ref "V12") (pin "2") (pinfunction "2_2") (pintype "passive"))
    )
    (net (code "55") (name "Net-(TP6-1)") (class "Default")
      (node (ref "ARDUINO_NANO") (pin "13") (pinfunction "~{RESET}_13") (pintype "input"))
      (node (ref "RESET1") (pin "1") (pinfunction "1_1") (pintype "passive"))
      (node (ref "TP6") (pin "P$1") (pinfunction "1_P$1") (pintype "bidirectional"))
    )
    (net (code "56") (name "VCC") (class "Default")
      (node (ref "ARDUINO_NANO") (pin "12") (pinfunction "5V_12") (pintype "power_in"))
      (node (ref "C3") (pin "1") (pinfunction "1_1") (pintype "passive"))
      (node (ref "C4") (pin "1") (pinfunction "1_1") (pintype "passive"))
      (node (ref "C5") (pin "1") (pinfunction "1_1") (pintype "passive"))
      (node (ref "C6") (pin "1") (pinfunction "1_1") (pintype "passive"))
      (node (ref "J1") (pin "2") (pinfunction "2_2") (pintype "power_in"))
      (node (ref "LDO") (pin "S") (pinfunction "VO_S") (pintype "passive"))
      (node (ref "P-MF") (pin "2") (pinfunction "S_2") (pintype "passive"))
      (node (ref "R2") (pin "2") (pinfunction "2_2") (pintype "passive"))
      (node (ref "R8") (pin "2") (pinfunction "2_2") (pintype "passive"))
      (node (ref "RTC") (pin "8") (pinfunction "VIN_8") (pintype "passive"))
      (node (ref "TP1") (pin "P$1") (pinfunction "1_P$1") (pintype "bidirectional"))
      (node (ref "VCC") (pin "1") (pinfunction "1_1") (pintype "passive"))
      (node (ref "VCC_OUT") (pin "1") (pinfunction "1_1") (pintype "passive"))
    )
    (net (code "57") (name "unconnected-(ARDUINO_NANO-3V3-Pad2)") (class "Default")
      (node (ref "ARDUINO_NANO") (pin "2") (pinfunction "3V3_2") (pintype "output"))
    )
    (net (code "58") (name "unconnected-(ARDUINO_NANO-AREF-Pad3)") (class "Default")
      (node (ref "ARDUINO_NANO") (pin "3") (pinfunction "AREF_3") (pintype "input"))
    )
    (net (code "59") (name "unconnected-(ARDUINO_NANO-RX0-Pad17)") (class "Default")
      (node (ref "ARDUINO_NANO") (pin "17") (pinfunction "RX0_17") (pintype "bidirectional"))
    )
    (net (code "60") (name "unconnected-(ARDUINO_NANO-TX1-Pad16)") (class "Default")
      (node (ref "ARDUINO_NANO") (pin "16") (pinfunction "TX1_16") (pintype "bidirectional"))
    )
    (net (code "61") (name "unconnected-(ARDUINO_NANO-~{RESET}-Pad18)") (class "Default")
      (node (ref "ARDUINO_NANO") (pin "18") (pinfunction "~{RESET}_18") (pintype "input"))
    )
    (net (code "62") (name "unconnected-(H1-MOUNT-PadB2,2)") (class "Default")
      (node (ref "H1") (pin "B2,2") (pinfunction "MOUNT_B2,2") (pintype "passive"))
    )
    (net (code "63") (name "unconnected-(H2-MOUNT-PadB2,2)") (class "Default")
      (node (ref "H2") (pin "B2,2") (pinfunction "MOUNT_B2,2") (pintype "passive"))
    )
    (net (code "64") (name "unconnected-(H3-MOUNT-PadB2,2)") (class "Default")
      (node (ref "H3") (pin "B2,2") (pinfunction "MOUNT_B2,2") (pintype "passive"))
    )
    (net (code "65") (name "unconnected-(H4-MOUNT-PadB2,2)") (class "Default")
      (node (ref "H4") (pin "B2,2") (pinfunction "MOUNT_B2,2") (pintype "passive"))
    )
    (net (code "66") (name "unconnected-(H5-MOUNT-PadB2,2)") (class "Default")
      (node (ref "H5") (pin "B2,2") (pinfunction "MOUNT_B2,2") (pintype "passive"))
    )
    (net (code "67") (name "unconnected-(H6-MOUNT-PadB2,2)") (class "Default")
      (node (ref "H6") (pin "B2,2") (pinfunction "MOUNT_B2,2") (pintype "passive"))
    )
  )
)
